# Jetson_power.net
KiCad netlist of a schematic drawn in Altium Designer
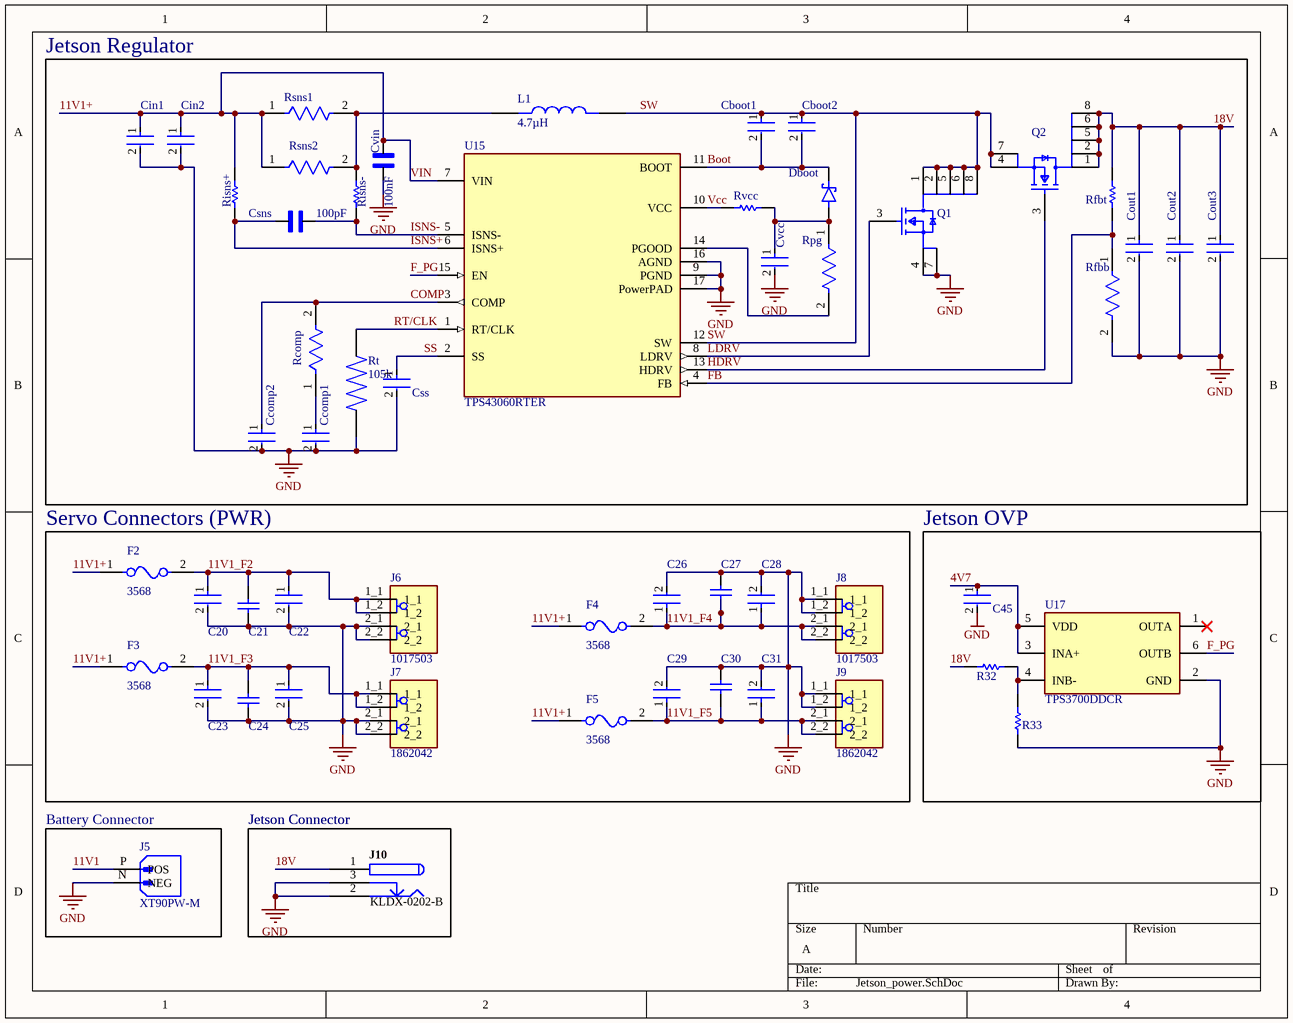
[diagram p0: Jetson_power.SchDoc]

(export (version "E")
  (design (tool "Eeschema 10.0.6"))
  (components
    (comp (ref "C20")
      (value "CL32A106KBJNNNE")
      (footprint "FP-CL32-IPC_B")
      (description "Cap Ceramic 10uF 50V X5R ±10% SMD 1210 +85°C Embossed T/R")
      (fields (field (name "TOLERANCE") "10%"))
      (libsource (lib "Altium Content Vault") (part "b4654b650e69147ec39a6b967a45e02"))
    )
    (comp (ref "C21")
      (value "C0805C105K5RACTU")
      (footprint "CAPC2013X140X50ML20T25")
      (fields (field (name "MANUFACTURER") "Kemet"))
      (libsource (lib "Altium Content Vault") (part "CAP"))
    )
    (comp (ref "C22")
      (value "CC0805KRX7R9BB104")
      (footprint "FP-CC0805-0_85-MFG")
      (description "CAP CER 0.1UF 50V X7R 0805")
      (fields (field (name "TOLERANCE") "0.1") (field (name "MANUFACTURER") "Yageo"))
      (libsource (lib "Altium Content Vault") (part "11868f565c42a9108669ba33697ecf6"))
    )
    (comp (ref "C23")
      (value "CL32A106KBJNNNE")
      (footprint "FP-CL32-IPC_B")
      (description "Cap Ceramic 10uF 50V X5R ±10% SMD 1210 +85°C Embossed T/R")
      (fields (field (name "TOLERANCE") "10%"))
      (libsource (lib "Altium Content Vault") (part "b4654b650e69147ec39a6b967a45e02"))
    )
    (comp (ref "C24")
      (value "C0805C105K5RACTU")
      (footprint "CAPC2013X140X50ML20T25")
      (fields (field (name "MANUFACTURER") "Kemet"))
      (libsource (lib "Altium Content Vault") (part "CAP"))
    )
    (comp (ref "C25")
      (value "CC0805KRX7R9BB104")
      (footprint "FP-CC0805-0_85-MFG")
      (description "CAP CER 0.1UF 50V X7R 0805")
      (fields (field (name "TOLERANCE") "0.1") (field (name "MANUFACTURER") "Yageo"))
      (libsource (lib "Altium Content Vault") (part "11868f565c42a9108669ba33697ecf6"))
    )
    (comp (ref "C26")
      (value "CL32A106KBJNNNE")
      (footprint "FP-CL32-IPC_B")
      (description "Cap Ceramic 10uF 50V X5R ±10% SMD 1210 +85°C Embossed T/R")
      (fields (field (name "TOLERANCE") "10%"))
      (libsource (lib "Altium Content Vault") (part "b4654b650e69147ec39a6b967a45e02"))
    )
    (comp (ref "C27")
      (value "C0805C105K5RACTU")
      (footprint "CAPC2013X140X50ML20T25")
      (fields (field (name "MANUFACTURER") "Kemet"))
      (libsource (lib "Altium Content Vault") (part "CAP"))
    )
    (comp (ref "C28")
      (value "CC0805KRX7R9BB104")
      (footprint "FP-CC0805-0_85-MFG")
      (description "CAP CER 0.1UF 50V X7R 0805")
      (fields (field (name "TOLERANCE") "0.1") (field (name "MANUFACTURER") "Yageo"))
      (libsource (lib "Altium Content Vault") (part "11868f565c42a9108669ba33697ecf6"))
    )
    (comp (ref "C29")
      (value "CL32A106KBJNNNE")
      (footprint "FP-CL32-IPC_B")
      (description "Cap Ceramic 10uF 50V X5R ±10% SMD 1210 +85°C Embossed T/R")
      (fields (field (name "TOLERANCE") "10%"))
      (libsource (lib "Altium Content Vault") (part "b4654b650e69147ec39a6b967a45e02"))
    )
    (comp (ref "C30")
      (value "C0805C105K5RACTU")
      (footprint "CAPC2013X140X50ML20T25")
      (fields (field (name "MANUFACTURER") "Kemet"))
      (libsource (lib "Altium Content Vault") (part "CAP"))
    )
    (comp (ref "C31")
      (value "CC0805KRX7R9BB104")
      (footprint "FP-CC0805-0_85-MFG")
      (description "CAP CER 0.1UF 50V X7R 0805")
      (fields (field (name "TOLERANCE") "0.1") (field (name "MANUFACTURER") "Yageo"))
      (libsource (lib "Altium Content Vault") (part "11868f565c42a9108669ba33697ecf6"))
    )
    (comp (ref "C45")
      (value "GRM155R71H104KE14D")
      (footprint "FP-GRM155-0_05-IPC_B")
      (description "Chip Multilayer Ceramic Capacitors for General Purpose, 0402, 0.10uF, X7R, 15%, 10%, 50V")
      (fields (field (name "VOLTAGE") "50V") (field (name "TOLERANCE") "10%"))
      (libsource (lib "Altium Content Vault") (part "02cd4be3c70576c341d710602a673aa"))
    )
    (comp (ref "Cboot1")
      (value "CC0805KRX7R9BB104")
      (footprint "FP-CC0805-0_85-MFG")
      (description "CAP CER 0.1UF 50V X7R 0805")
      (fields (field (name "TOLERANCE") "0.1") (field (name "MANUFACTURER") "Yageo"))
      (libsource (lib "Altium Content Vault") (part "11868f565c42a9108669ba33697ecf6"))
    )
    (comp (ref "Cboot2")
      (value "CC0805KRX7R9BB104")
      (footprint "FP-CC0805-0_85-MFG")
      (description "CAP CER 0.1UF 50V X7R 0805")
      (fields (field (name "TOLERANCE") "0.1") (field (name "MANUFACTURER") "Yageo"))
      (libsource (lib "Altium Content Vault") (part "11868f565c42a9108669ba33697ecf6"))
    )
    (comp (ref "Ccomp1")
      (value "CGA4C2C0G1H822J060AA")
      (footprint "FP-CGA4J-IPC_A")
      (description "Cap Ceramic 8.2nF 50V C0G 5% Pad SMD 0805 +125°C Automotive T/R")
      (fields (field (name "TOLERANCE") "5%"))
      (libsource (lib "Altium Content Vault") (part "b4654b650e69147ec39a6b967a45e02"))
    )
    (comp (ref "Ccomp2")
      (value "GRM1555C1H391JA01J")
      (footprint "FP-GRM155-0_05-IPC_A")
      (description "Chip Multilayer Ceramic Capacitors for General Purpose, 0402, 390pF, C0G, 30ppm/°C, 5%, 50V")
      (fields (field (name "VOLTAGE") "50V") (field (name "TOLERANCE") "5%"))
      (libsource (lib "Altium Content Vault") (part "02cd4be3c70576c341d710602a673aa"))
    )
    (comp (ref "Cin1")
      (value "CL32A106KBJNNNE")
      (footprint "FP-CL32-IPC_B")
      (description "Cap Ceramic 10uF 50V X5R ±10% SMD 1210 +85°C Embossed T/R")
      (fields (field (name "TOLERANCE") "10%"))
      (libsource (lib "Altium Content Vault") (part "b4654b650e69147ec39a6b967a45e02"))
    )
    (comp (ref "Cin2")
      (value "CL32A106KBJNNNE")
      (footprint "FP-CL32-IPC_B")
      (description "Cap Ceramic 10uF 50V X5R ±10% SMD 1210 +85°C Embossed T/R")
      (fields (field (name "TOLERANCE") "10%"))
      (libsource (lib "Altium Content Vault") (part "b4654b650e69147ec39a6b967a45e02"))
    )
    (comp (ref "Cout1")
      (value "CL32B106KBJNNWE")
      (footprint "FP-CL32-IPC_B")
      (description "Cap Ceramic 10uF 50V X7R ±10% SMD 1210 +125°C Embossed T/R")
      (fields (field (name "TOLERANCE") "10%"))
      (libsource (lib "Altium Content Vault") (part "b4654b650e69147ec39a6b967a45e02"))
    )
    (comp (ref "Cout2")
      (value "CL32B106KBJNNWE")
      (footprint "FP-CL32-IPC_B")
      (description "Cap Ceramic 10uF 50V X7R ±10% SMD 1210 +125°C Embossed T/R")
      (fields (field (name "TOLERANCE") "10%"))
      (libsource (lib "Altium Content Vault") (part "b4654b650e69147ec39a6b967a45e02"))
    )
    (comp (ref "Cout3")
      (value "CL32B106KBJNNWE")
      (footprint "FP-CL32-IPC_B")
      (description "Cap Ceramic 10uF 50V X7R ±10% SMD 1210 +125°C Embossed T/R")
      (fields (field (name "TOLERANCE") "10%"))
      (libsource (lib "Altium Content Vault") (part "b4654b650e69147ec39a6b967a45e02"))
    )
    (comp (ref "Csns")
      (value "100pF")
      (footprint "CAPC1608X90N")
      (description "SMD Capacitor C0G(EIA) with Capacitance: 100pF Tol. 5%. Rated Voltage: 50Vdc")
      (fields (field (name "MF") "Murata Electronics") (field (name "MP") "GRM1885C1H101JA01D"))
      (libsource (lib "Bryan Heddle") (part "GRM1885C1H101JA01D"))
    )
    (comp (ref "Css")
      (value "GRM155R71H104KE14D")
      (footprint "FP-GRM155-0_05-IPC_B")
      (description "Chip Multilayer Ceramic Capacitors for General Purpose, 0402, 0.10uF, X7R, 15%, 10%, 50V")
      (fields (field (name "VOLTAGE") "50V") (field (name "TOLERANCE") "10%"))
      (libsource (lib "Altium Content Vault") (part "02cd4be3c70576c341d710602a673aa"))
    )
    (comp (ref "Cvcc")
      (value "GRM188R61C106MA73D")
      (footprint "FP-GRM188-0_2-IPC_A")
      (description "Chip Multilayer Ceramic Capacitors for General Purpose, 0603, 10uF, X5R, 15%, 20%, 16V")
      (fields (field (name "TOLERANCE") "20%") (field (name "VOLTAGE") "16V"))
      (libsource (lib "Altium Content Vault") (part "11868f565c42a9108669ba33697ecf6"))
    )
    (comp (ref "Cvin")
      (value "100nF")
      (footprint "CAPC1005X55N")
      (description "SMD Capacitor X7R(EIA) with Capacitance: 0.10uF Tol. 10%. Rated Voltage: 16Vdc")
      (fields (field (name "MP") "GRM155R71C104KA88D") (field (name "MF") "Murata"))
      (libsource (lib "Bryan Heddle") (part "GRM155R71C104KA88D"))
    )
    (comp (ref "Dboot")
      (value "XBS053V15R-G")
      (footprint "DIO_XBS053V15R-G")
      (description "Diode Schottky 20V 500mA Surface Mount SOD-523")
      (fields (field (name "MF") "Torex") (field (name "DIGI-KEY_PART_NUMBER") "XBS053V15R-G-ND"))
      (libsource (lib "Bryan Heddle") (part "XBS053V15R-G"))
    )
    (comp (ref "F2")
      (value "3568")
      (footprint "FP-3568-MFG")
      (fields (field (name "VOLTAGE") "500V"))
      (libsource (lib "Altium Content Vault") (part "3568"))
    )
    (comp (ref "F3")
      (value "3568")
      (footprint "FP-3568-MFG")
      (fields (field (name "VOLTAGE") "500V"))
      (libsource (lib "Altium Content Vault") (part "3568"))
    )
    (comp (ref "F4")
      (value "3568")
      (footprint "FP-3568-MFG")
      (fields (field (name "VOLTAGE") "500V"))
      (libsource (lib "Altium Content Vault") (part "3568"))
    )
    (comp (ref "F5")
      (value "3568")
      (footprint "FP-3568-MFG")
      (fields (field (name "VOLTAGE") "500V"))
      (libsource (lib "Altium Content Vault") (part "3568"))
    )
    (comp (ref "J5")
      (value "XT90PW-M")
      (footprint "AMASS_XT90PW-M - duplicate")
      (description "Socket; DC supply; XT90; male; PIN: 2; on PCBs; THT; Colour: yellow")
      (fields (field (name "MF") "AMASS"))
      (libsource (lib "AI_Project_Library") (part "XT90PW-M"))
    )
    (comp (ref "J6")
      (value "1017503")
      (footprint "PHOENIX_1017503")
      (libsource (lib "Bryan Heddle") (part "1017503"))
    )
    (comp (ref "J7")
      (value "1862042")
      (footprint "PHOENIX_1862042")
      (fields (field (name "MF") "{'manufacturer': u'Phoenix Contact'}"))
      (libsource (lib "Bryan Heddle") (part "1862042"))
    )
    (comp (ref "J8")
      (value "1017503")
      (footprint "PHOENIX_1017503")
      (libsource (lib "Bryan Heddle") (part "1017503"))
    )
    (comp (ref "J9")
      (value "1862042")
      (footprint "PHOENIX_1862042")
      (fields (field (name "MF") "{'manufacturer': u'Phoenix Contact'}"))
      (libsource (lib "Bryan Heddle") (part "1862042"))
    )
    (comp (ref "J10")
      (value "KLDX-0202-B")
      (footprint "KYCN-KLDX-0202-B_V")
      (description "3 Conductor Power Jack, 2 break 2 aux contacts")
      (libsource (lib "Altium Content Vault") (part "KYCN-KLDX-0202-B-3"))
    )
    (comp (ref "L1")
      (value "4.7µH")
      (footprint "IND_XAL6060-472MEB")
      (description "Power inductor, shielded, 20% tol, SMT, RoHS, halogen-f")
      (fields (field (name "MF") "Coilcraft") (field (name "MP") "XAL6060-472MEB"))
      (libsource (lib "Bryan Heddle") (part "XAL6060-472MEB"))
    )
    (comp (ref "Q1")
      (value "CSD17571Q2")
      (footprint "FP-DQK0006C-MFG")
      (description "MOSFET N-CH 30V 22A 6SON")
      (libsource (lib "Altium Content Vault") (part "67f8c6576a35c08c1e5776583238e4f"))
    )
    (comp (ref "Q2")
      (value "CSD17571Q2")
      (footprint "FP-DQK0006C-MFG")
      (description "MOSFET N-CH 30V 22A 6SON")
      (libsource (lib "Altium Content Vault") (part "67f8c6576a35c08c1e5776583238e4f"))
    )
    (comp (ref "R32")
      (value "CRCW0402475KFKED")
      (footprint "RESC1005X40X25LL05T05")
      (fields (field (name "MANUFACTURER") "Vishay Dale"))
      (libsource (lib "Altium Content Vault") (part "RES"))
    )
    (comp (ref "R33")
      (value "CRCW040210K0FKEDHP")
      (footprint "RESC1005X40X25ML05T10")
      (fields (field (name "MANUFACTURER") "Vishay Dale"))
      (libsource (lib "Altium Content Vault") (part "RES"))
    )
    (comp (ref "Rcomp")
      (value "CRCW04025K36FKED")
      (footprint "FP-CRCW0402-e3-IPC_B")
      (description "RES Thick Film, 5.36kΩ, 1%, 0.063W, 100ppm/°C, 0402")
      (fields (field (name "TOLERANCE") "1%"))
      (libsource (lib "Altium Content Vault") (part "1029c3af85768c4190bb7ad29bc67b5"))
    )
    (comp (ref "Rfbb")
      (value "CRCW040211K0FKED")
      (footprint "FP-CRCW0402-e3-IPC_A")
      (description "RES Thick Film, 11kΩ, 1%, 0.063W, 100ppm/°C, 0402")
      (fields (field (name "TOLERANCE") "1%"))
      (libsource (lib "Altium Content Vault") (part "1029c3af85768c4190bb7ad29bc67b5"))
    )
    (comp (ref "Rfbt")
      (value "CRCW0402150KFKED")
      (footprint "RESC1005X40X25NL05T05")
      (fields (field (name "MANUFACTURER") "Vishay Dale"))
      (libsource (lib "Altium Content Vault") (part "RES"))
    )
    (comp (ref "Risns+")
      (value "CRCW040210R0FKED")
      (footprint "RESC1005X40X25NL05T05")
      (fields (field (name "MANUFACTURER") "Vishay Dale"))
      (libsource (lib "Altium Content Vault") (part "RES"))
    )
    (comp (ref "Risns-")
      (value "CRCW040210R0FKED")
      (footprint "RESC1005X40X25NL05T05")
      (fields (field (name "MANUFACTURER") "Vishay Dale"))
      (libsource (lib "Altium Content Vault") (part "RES"))
    )
    (comp (ref "Rpg")
      (value "CRCW0402100KFKED")
      (footprint "FP-CRCW0402-e3-IPC_C")
      (description "RES Thick Film, 100kΩ, 1%, 0.063W, 100ppm/°C, 0402")
      (fields (field (name "TOLERANCE") "1%"))
      (libsource (lib "Altium Content Vault") (part "1029c3af85768c4190bb7ad29bc67b5"))
    )
    (comp (ref "Rsns1")
      (value "PRL1632-R010-F-T1")
      (footprint "FP-PRL1632-MFG")
      (description "10 mOhms ±1% 1W Chip Resistor Wide 0612 (1632 Metric), Current Sense Thin Film")
      (fields (field (name "TOLERANCE") "1%"))
      (libsource (lib "Altium Content Vault") (part "1029c3af85768c4190bb7ad29bc67b5"))
    )
    (comp (ref "Rsns2")
      (value "PRL1632-R010-F-T1")
      (footprint "FP-PRL1632-MFG")
      (description "10 mOhms ±1% 1W Chip Resistor Wide 0612 (1632 Metric), Current Sense Thin Film")
      (fields (field (name "TOLERANCE") "1%"))
      (libsource (lib "Altium Content Vault") (part "1029c3af85768c4190bb7ad29bc67b5"))
    )
    (comp (ref "Rt")
      (value "105k")
      (footprint "RESC0603X26N")
      (description "105 kOhms Â±1% 0.05W, 1/20W Chip Resistor 0201 (0603 Metric) Moisture Resistant Thick Film")
      (fields (field (name "MF") "Yageo") (field (name "MP") "RC0201FR-07105KL"))
      (libsource (lib "Bryan Heddle") (part "RC0201FR-07105KL"))
    )
    (comp (ref "Rvcc")
      (value "CRCW04022R00FKED")
      (footprint "RESC1005X40X25ML05T05")
      (fields (field (name "MANUFACTURER") "Vishay Dale"))
      (libsource (lib "Altium Content Vault") (part "RES"))
    )
    (comp (ref "U15")
      (value "TPS43060RTER")
      (footprint "FP-RTE0016E-IPC_B")
      (description "IC REG CTRLR BOOST 16WQFN")
      (libsource (lib "Altium Content Vault") (part "c5c4772e39b7b1cdf4ed7dbfc316528"))
    )
    (comp (ref "U17")
      (value "TPS3700DDCR")
      (footprint "FP-DDC0006A-IPC_A")
      (description "IC COMP WINDOW W/REF 6SOT")
      (libsource (lib "Altium Content Vault") (part "11b8ec840a671e65fa4eb3078aa3645"))
    )
  )
  (nets
    (net (code "1") (name "/4V7") (class "Default")
      (node (ref "C45") (pin "1") (pinfunction "1_1") (pintype "passive"))
      (node (ref "U17") (pin "3") (pinfunction "INA+_3") (pintype "tri_state"))
      (node (ref "U17") (pin "5") (pinfunction "VDD_5") (pintype "power_in"))
    )
    (net (code "2") (name "/11V1") (class "Default")
      (node (ref "J5") (pin "P") (pinfunction "POS_P") (pintype "passive"))
    )
    (net (code "3") (name "/11V1+") (class "Default")
      (node (ref "Cin1") (pin "1") (pinfunction "1_1") (pintype "passive"))
      (node (ref "Cin2") (pin "1") (pinfunction "1_1") (pintype "passive"))
      (node (ref "Cvin") (pin "2") (pinfunction "2_2") (pintype "passive"))
      (node (ref "F2") (pin "1") (pinfunction "1_1") (pintype "passive"))
      (node (ref "F3") (pin "1") (pinfunction "1_1") (pintype "passive"))
      (node (ref "F4") (pin "1") (pinfunction "1_1") (pintype "passive"))
      (node (ref "F5") (pin "1") (pinfunction "1_1") (pintype "passive"))
      (node (ref "Risns+") (pin "1") (pinfunction "1_1") (pintype "passive"))
      (node (ref "Rsns1") (pin "1") (pinfunction "1_1") (pintype "passive"))
      (node (ref "Rsns2") (pin "1") (pinfunction "1_1") (pintype "passive"))
      (node (ref "U15") (pin "7") (pinfunction "VIN_7") (pintype "power_in"))
    )
    (net (code "4") (name "/11V1_F2") (class "Default")
      (node (ref "C20") (pin "1") (pinfunction "1_1") (pintype "passive"))
      (node (ref "C21") (pin "2") (pinfunction "2_2") (pintype "passive"))
      (node (ref "C22") (pin "1") (pinfunction "1_1") (pintype "passive"))
      (node (ref "F2") (pin "2") (pinfunction "2_2") (pintype "passive"))
      (node (ref "J6") (pin "1_1") (pinfunction "1_1_1_1") (pintype "passive"))
      (node (ref "J6") (pin "1_2") (pinfunction "1_2_1_2") (pintype "passive"))
    )
    (net (code "5") (name "/11V1_F3") (class "Default")
      (node (ref "C23") (pin "1") (pinfunction "1_1") (pintype "passive"))
      (node (ref "C24") (pin "2") (pinfunction "2_2") (pintype "passive"))
      (node (ref "C25") (pin "1") (pinfunction "1_1") (pintype "passive"))
      (node (ref "F3") (pin "2") (pinfunction "2_2") (pintype "passive"))
      (node (ref "J7") (pin "1_1") (pinfunction "1_1_1_1") (pintype "passive"))
      (node (ref "J7") (pin "1_2") (pinfunction "1_2_1_2") (pintype "passive"))
    )
    (net (code "6") (name "/11V1_F4") (class "Default")
      (node (ref "C26") (pin "1") (pinfunction "1_1") (pintype "passive"))
      (node (ref "C27") (pin "2") (pinfunction "2_2") (pintype "passive"))
      (node (ref "C28") (pin "1") (pinfunction "1_1") (pintype "passive"))
      (node (ref "F4") (pin "2") (pinfunction "2_2") (pintype "passive"))
      (node (ref "J8") (pin "2_1") (pinfunction "2_1_2_1") (pintype "passive"))
      (node (ref "J8") (pin "2_2") (pinfunction "2_2_2_2") (pintype "passive"))
    )
    (net (code "7") (name "/11V1_F5") (class "Default")
      (node (ref "C29") (pin "1") (pinfunction "1_1") (pintype "passive"))
      (node (ref "C30") (pin "2") (pinfunction "2_2") (pintype "passive"))
      (node (ref "C31") (pin "1") (pinfunction "1_1") (pintype "passive"))
      (node (ref "F5") (pin "2") (pinfunction "2_2") (pintype "passive"))
      (node (ref "J9") (pin "2_1") (pinfunction "2_1_2_1") (pintype "passive"))
      (node (ref "J9") (pin "2_2") (pinfunction "2_2_2_2") (pintype "passive"))
    )
    (net (code "8") (name "/18V") (class "Default")
      (node (ref "Cout1") (pin "1") (pinfunction "1_1") (pintype "passive"))
      (node (ref "Cout2") (pin "1") (pinfunction "1_1") (pintype "passive"))
      (node (ref "Cout3") (pin "1") (pinfunction "1_1") (pintype "passive"))
      (node (ref "J10") (pin "1") (pintype "power_in"))
      (node (ref "Q2") (pin "1") (pinfunction "D_1") (pintype "passive"))
      (node (ref "Q2") (pin "2") (pinfunction "D_2") (pintype "passive"))
      (node (ref "Q2") (pin "5") (pinfunction "D_5") (pintype "passive"))
      (node (ref "Q2") (pin "6") (pinfunction "D_6") (pintype "passive"))
      (node (ref "Q2") (pin "8") (pinfunction "D_8") (pintype "passive"))
      (node (ref "R32") (pin "1") (pinfunction "1_1") (pintype "passive"))
      (node (ref "Rfbt") (pin "2") (pinfunction "2_2") (pintype "passive"))
    )
    (net (code "9") (name "/Boot") (class "Default")
      (node (ref "Cboot1") (pin "2") (pinfunction "2_2") (pintype "passive"))
      (node (ref "Cboot2") (pin "2") (pinfunction "2_2") (pintype "passive"))
      (node (ref "Dboot") (pin "C") (pinfunction "K_C") (pintype "passive"))
      (node (ref "U15") (pin "11") (pinfunction "BOOT_11") (pintype "passive"))
    )
    (net (code "10") (name "/COMP") (class "Default")
      (node (ref "Ccomp2") (pin "1") (pinfunction "1_1") (pintype "passive"))
      (node (ref "Rcomp") (pin "2") (pinfunction "2_2") (pintype "passive"))
      (node (ref "U15") (pin "3") (pinfunction "COMP_3") (pintype "output"))
    )
    (net (code "11") (name "/FB") (class "Default")
      (node (ref "Rfbb") (pin "1") (pinfunction "1_1") (pintype "passive"))
      (node (ref "Rfbt") (pin "1") (pinfunction "1_1") (pintype "passive"))
      (node (ref "U15") (pin "4") (pinfunction "FB_4") (pintype "input"))
    )
    (net (code "12") (name "/F_PG") (class "Default")
      (node (ref "U15") (pin "15") (pinfunction "EN_15") (pintype "input"))
      (node (ref "U17") (pin "6") (pinfunction "OUTB_6") (pintype "open_collector"))
    )
    (net (code "13") (name "/HDRV") (class "Default")
      (node (ref "Q2") (pin "3") (pinfunction "G_3") (pintype "passive"))
      (node (ref "U15") (pin "13") (pinfunction "HDRV_13") (pintype "output"))
    )
    (net (code "14") (name "/ISNS+") (class "Default")
      (node (ref "Csns") (pin "1") (pinfunction "1_1") (pintype "passive"))
      (node (ref "Risns+") (pin "2") (pinfunction "2_2") (pintype "passive"))
      (node (ref "U15") (pin "6") (pinfunction "ISNS+_6") (pintype "tri_state"))
    )
    (net (code "15") (name "/ISNS-") (class "Default")
      (node (ref "Csns") (pin "2") (pinfunction "2_2") (pintype "passive"))
      (node (ref "Risns-") (pin "1") (pinfunction "1_1") (pintype "passive"))
      (node (ref "U15") (pin "5") (pinfunction "ISNS-_5") (pintype "tri_state"))
    )
    (net (code "16") (name "/LDRV") (class "Default")
      (node (ref "Q1") (pin "3") (pinfunction "G_3") (pintype "passive"))
      (node (ref "U15") (pin "8") (pinfunction "LDRV_8") (pintype "output"))
    )
    (net (code "17") (name "/RT{slash}CLK") (class "Default")
      (node (ref "Rt") (pin "1") (pinfunction "1_1") (pintype "passive"))
      (node (ref "U15") (pin "1") (pinfunction "RT/CLK_1") (pintype "input"))
    )
    (net (code "18") (name "/SS") (class "Default")
      (node (ref "Css") (pin "1") (pinfunction "1_1") (pintype "passive"))
      (node (ref "U15") (pin "2") (pinfunction "SS_2") (pintype "passive"))
    )
    (net (code "19") (name "/SW") (class "Default")
      (node (ref "Cboot1") (pin "1") (pinfunction "1_1") (pintype "passive"))
      (node (ref "Cboot2") (pin "1") (pinfunction "1_1") (pintype "passive"))
      (node (ref "L1") (pin "2") (pinfunction "2_2") (pintype "passive"))
      (node (ref "Q1") (pin "1") (pinfunction "D_1") (pintype "passive"))
      (node (ref "Q1") (pin "2") (pinfunction "D_2") (pintype "passive"))
      (node (ref "Q1") (pin "5") (pinfunction "D_5") (pintype "passive"))
      (node (ref "Q1") (pin "6") (pinfunction "D_6") (pintype "passive"))
      (node (ref "Q1") (pin "8") (pinfunction "D_8") (pintype "passive"))
      (node (ref "Q2") (pin "4") (pinfunction "S_4") (pintype "passive"))
      (node (ref "Q2") (pin "7") (pinfunction "S_7") (pintype "passive"))
      (node (ref "U15") (pin "12") (pinfunction "SW_12") (pintype "passive"))
    )
    (net (code "20") (name "/Vcc") (class "Default")
      (node (ref "Rvcc") (pin "1") (pinfunction "1_1") (pintype "passive"))
      (node (ref "U15") (pin "10") (pinfunction "VCC_10") (pintype "power_in"))
    )
    (net (code "21") (name "GND") (class "Default")
      (node (ref "C20") (pin "2") (pinfunction "2_2") (pintype "passive"))
      (node (ref "C21") (pin "1") (pinfunction "1_1") (pintype "passive"))
      (node (ref "C22") (pin "2") (pinfunction "2_2") (pintype "passive"))
      (node (ref "C23") (pin "2") (pinfunction "2_2") (pintype "passive"))
      (node (ref "C24") (pin "1") (pinfunction "1_1") (pintype "passive"))
      (node (ref "C25") (pin "2") (pinfunction "2_2") (pintype "passive"))
      (node (ref "C26") (pin "2") (pinfunction "2_2") (pintype "passive"))
      (node (ref "C27") (pin "1") (pinfunction "1_1") (pintype "passive"))
      (node (ref "C28") (pin "2") (pinfunction "2_2") (pintype "passive"))
      (node (ref "C29") (pin "2") (pinfunction "2_2") (pintype "passive"))
      (node (ref "C30") (pin "1") (pinfunction "1_1") (pintype "passive"))
      (node (ref "C31") (pin "2") (pinfunction "2_2") (pintype "passive"))
      (node (ref "C45") (pin "2") (pinfunction "2_2") (pintype "passive"))
      (node (ref "Ccomp1") (pin "2") (pinfunction "2_2") (pintype "passive"))
      (node (ref "Ccomp2") (pin "2") (pinfunction "2_2") (pintype "passive"))
      (node (ref "Cin1") (pin "2") (pinfunction "2_2") (pintype "passive"))
      (node (ref "Cin2") (pin "2") (pinfunction "2_2") (pintype "passive"))
      (node (ref "Cout1") (pin "2") (pinfunction "2_2") (pintype "passive"))
      (node (ref "Cout2") (pin "2") (pinfunction "2_2") (pintype "passive"))
      (node (ref "Cout3") (pin "2") (pinfunction "2_2") (pintype "passive"))
      (node (ref "Css") (pin "2") (pinfunction "2_2") (pintype "passive"))
      (node (ref "Cvcc") (pin "2") (pinfunction "2_2") (pintype "passive"))
      (node (ref "Cvin") (pin "1") (pinfunction "1_1") (pintype "passive"))
      (node (ref "J10") (pin "2") (pintype "power_in"))
      (node (ref "J10") (pin "3") (pintype "power_in"))
      (node (ref "J5") (pin "N") (pinfunction "NEG_N") (pintype "passive"))
      (node (ref "J6") (pin "2_1") (pinfunction "2_1_2_1") (pintype "passive"))
      (node (ref "J6") (pin "2_2") (pinfunction "2_2_2_2") (pintype "passive"))
      (node (ref "J7") (pin "2_1") (pinfunction "2_1_2_1") (pintype "passive"))
      (node (ref "J7") (pin "2_2") (pinfunction "2_2_2_2") (pintype "passive"))
      (node (ref "J8") (pin "1_1") (pinfunction "1_1_1_1") (pintype "passive"))
      (node (ref "J8") (pin "1_2") (pinfunction "1_2_1_2") (pintype "passive"))
      (node (ref "J9") (pin "1_1") (pinfunction "1_1_1_1") (pintype "passive"))
      (node (ref "J9") (pin "1_2") (pinfunction "1_2_1_2") (pintype "passive"))
      (node (ref "Q1") (pin "4") (pinfunction "S_4") (pintype "passive"))
      (node (ref "Q1") (pin "7") (pinfunction "S_7") (pintype "passive"))
      (node (ref "R33") (pin "2") (pinfunction "2_2") (pintype "passive"))
      (node (ref "Rfbb") (pin "2") (pinfunction "2_2") (pintype "passive"))
      (node (ref "Rt") (pin "2") (pinfunction "2_2") (pintype "passive"))
      (node (ref "U15") (pin "16") (pinfunction "AGND_16") (pintype "power_in"))
      (node (ref "U15") (pin "17") (pinfunction "PowerPAD_17") (pintype "power_in"))
      (node (ref "U15") (pin "9") (pinfunction "PGND_9") (pintype "power_in"))
      (node (ref "U17") (pin "2") (pinfunction "GND_2") (pintype "power_in"))
    )
    (net (code "22") (name "Net-(Ccomp1-Pad1)") (class "Default")
      (node (ref "Ccomp1") (pin "1") (pinfunction "1_1") (pintype "passive"))
      (node (ref "Rcomp") (pin "1") (pinfunction "1_1") (pintype "passive"))
    )
    (net (code "23") (name "Net-(Cvcc-Pad1)") (class "Default")
      (node (ref "Cvcc") (pin "1") (pinfunction "1_1") (pintype "passive"))
      (node (ref "Dboot") (pin "A") (pinfunction "A_A") (pintype "passive"))
      (node (ref "Rpg") (pin "1") (pinfunction "1_1") (pintype "passive"))
      (node (ref "Rvcc") (pin "2") (pinfunction "2_2") (pintype "passive"))
    )
    (net (code "24") (name "Net-(L1-Pad1)") (class "Default")
      (node (ref "L1") (pin "1") (pinfunction "1_1") (pintype "passive"))
      (node (ref "Risns-") (pin "2") (pinfunction "2_2") (pintype "passive"))
      (node (ref "Rsns1") (pin "2") (pinfunction "2_2") (pintype "passive"))
      (node (ref "Rsns2") (pin "2") (pinfunction "2_2") (pintype "passive"))
    )
    (net (code "25") (name "Net-(U15-PGOOD)") (class "Default")
      (node (ref "Rpg") (pin "2") (pinfunction "2_2") (pintype "passive"))
      (node (ref "U15") (pin "14") (pinfunction "PGOOD_14") (pintype "open_collector"))
    )
    (net (code "26") (name "Net-(U17-INB-)") (class "Default")
      (node (ref "R32") (pin "2") (pinfunction "2_2") (pintype "passive"))
      (node (ref "R33") (pin "1") (pinfunction "1_1") (pintype "passive"))
      (node (ref "U17") (pin "4") (pinfunction "INB-_4") (pintype "tri_state"))
    )
    (net (code "27") (name "unconnected-(U17-OUTA-Pad1)") (class "Default")
      (node (ref "U17") (pin "1") (pinfunction "OUTA_1") (pintype "open_collector+no_connect"))
    )
  )
)
